# source_eagle.net
KiCad netlist of a schematic drawn in EAGLE
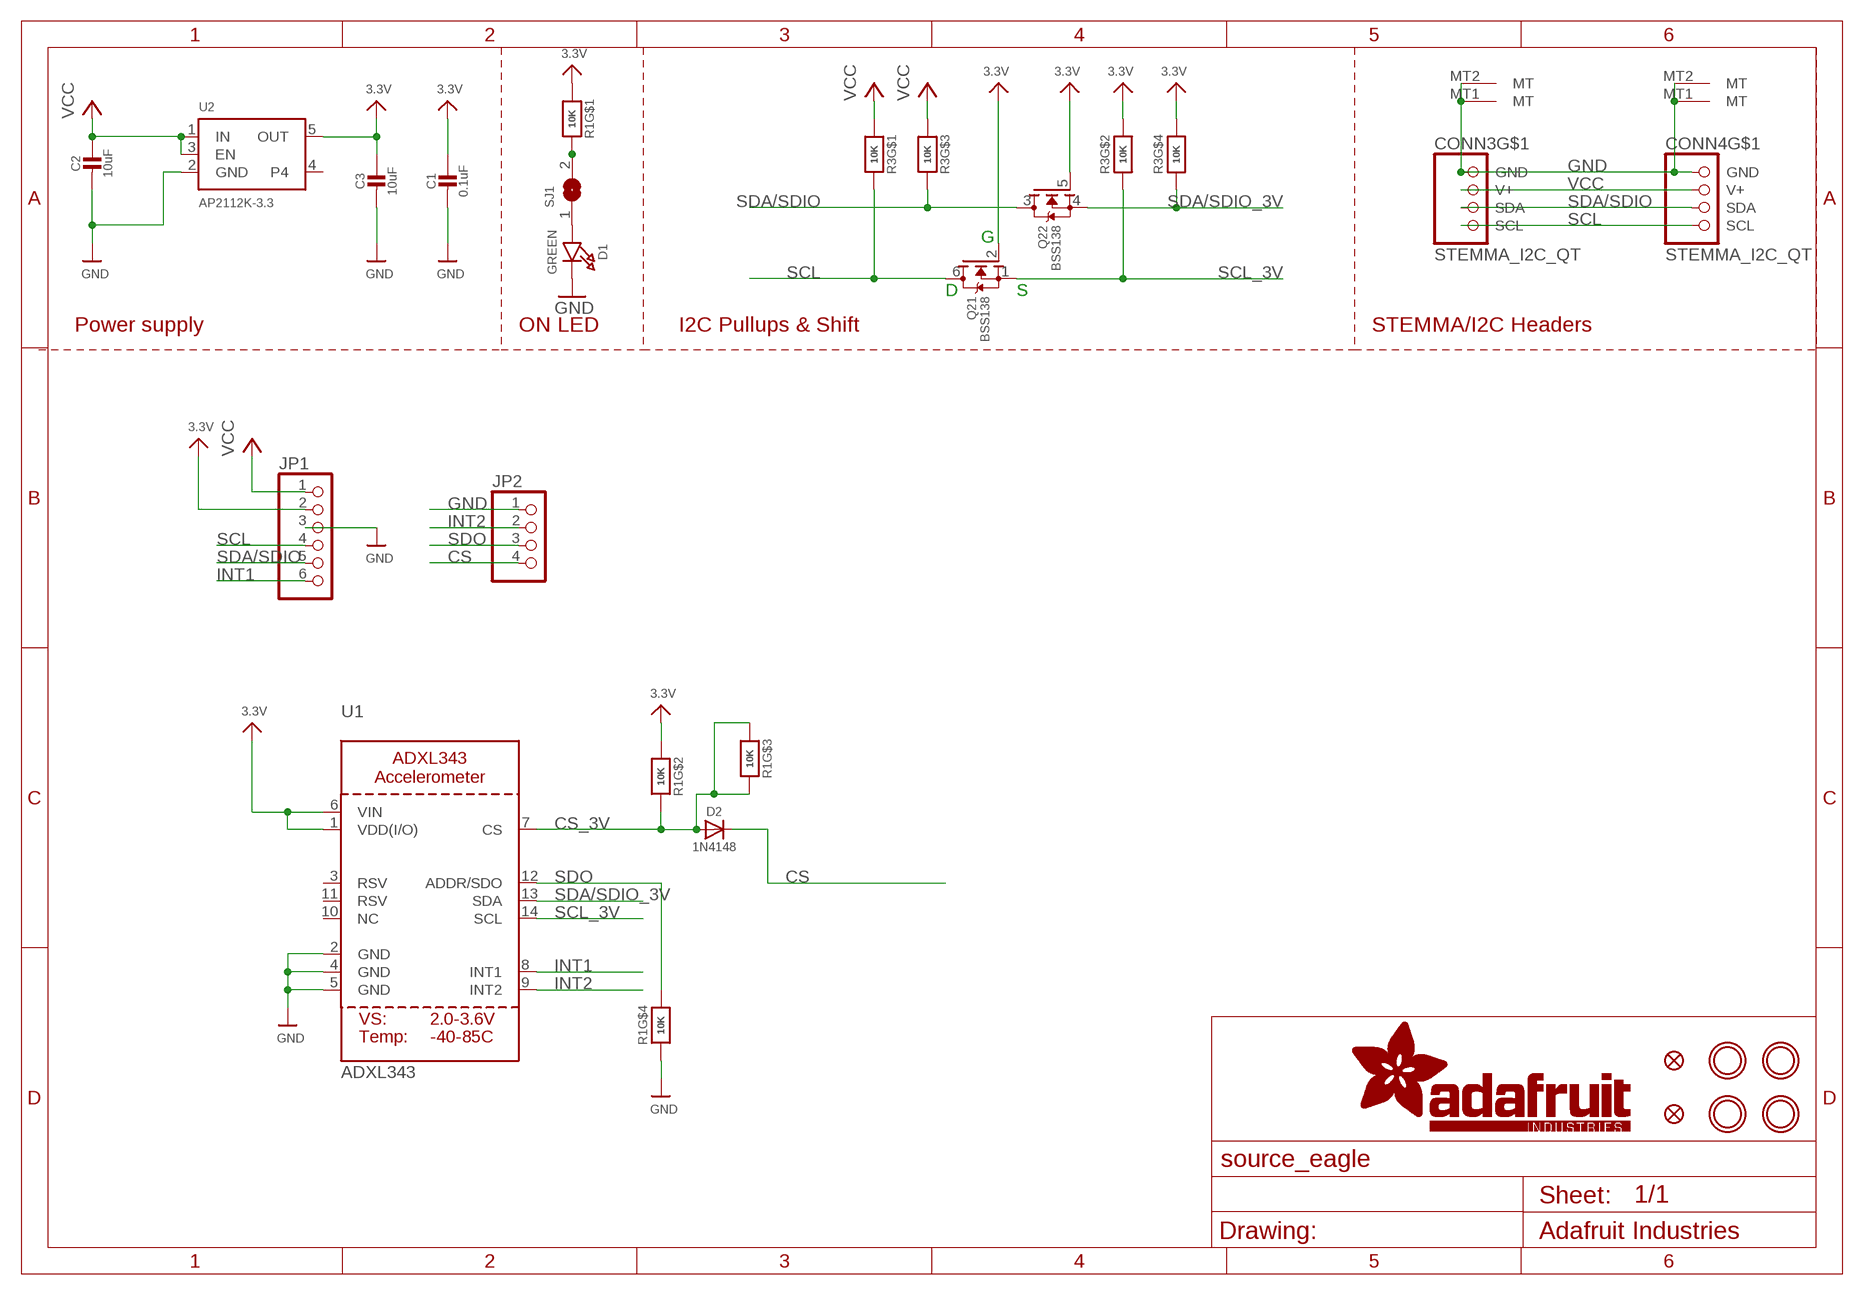
[diagram p0: schematic, sheet 1]

(export (version "E")
  (design (tool "Eeschema 10.0.6"))
  (components
    (comp (ref "C1")
      (value "0.1uF")
      (footprint "eagle-import:0603-NO")
      (libsource (lib "eagle-import") (part "CAP_CERAMIC0603_NO"))
    )
    (comp (ref "C2")
      (value "10uF")
      (footprint "eagle-import:_0805MP")
      (libsource (lib "eagle-import") (part "CAP_CERAMIC_0805MP"))
    )
    (comp (ref "C3")
      (value "10uF")
      (footprint "eagle-import:0805-NO")
      (libsource (lib "eagle-import") (part "CAP_CERAMIC0805-NOOUTLINE"))
    )
    (comp (ref "CONN3")
      (value "STEMMA_I2C_QT")
      (footprint "eagle-import:JST_SH4")
      (libsource (lib "eagle-import") (part "STEMMA_I2C_QT"))
    )
    (comp (ref "CONN4")
      (value "STEMMA_I2C_QT")
      (footprint "eagle-import:JST_SH4")
      (libsource (lib "eagle-import") (part "STEMMA_I2C_QT"))
    )
    (comp (ref "D1")
      (value "GREEN")
      (footprint "eagle-import:CHIPLED_0603_NOOUTLINE")
      (libsource (lib "eagle-import") (part "LED0603_NOOUTLINE"))
    )
    (comp (ref "D2")
      (value "1N4148")
      (footprint "eagle-import:SOD-323")
      (libsource (lib "eagle-import") (part "DIODESOD-323"))
    )
    (comp (ref "FID3")
      (value "FIDUCIAL_1MM")
      (footprint "eagle-import:FIDUCIAL_1MM")
      (libsource (lib "eagle-import") (part "FIDUCIAL_1MM"))
    )
    (comp (ref "FID4")
      (value "FIDUCIAL_1MM")
      (footprint "eagle-import:FIDUCIAL_1MM")
      (libsource (lib "eagle-import") (part "FIDUCIAL_1MM"))
    )
    (comp (ref "JP1")
      (value "HEADER-1X670MIL")
      (footprint "eagle-import:1X06_ROUND_70")
      (libsource (lib "eagle-import") (part "HEADER-1X670MIL"))
    )
    (comp (ref "JP2")
      (value "HEADER-1X4ROUND")
      (footprint "eagle-import:1X04_ROUND")
      (libsource (lib "eagle-import") (part "HEADER-1X4ROUND"))
    )
    (comp (ref "Q2")
      (value "BSS138")
      (footprint "eagle-import:SOT363")
      (libsource (lib "eagle-import") (part "MOSFET-N_DUAL"))
    )
    (comp (ref "R1")
      (value "10K")
      (footprint "eagle-import:RESPACK_4X0603")
      (libsource (lib "eagle-import") (part "RESISTOR_4PACK"))
    )
    (comp (ref "R3")
      (value "10K")
      (footprint "eagle-import:RESPACK_4X0603")
      (libsource (lib "eagle-import") (part "RESISTOR_4PACK"))
    )
    (comp (ref "SJ1")
      (value "SOLDERJUMPERCLOSED")
      (footprint "eagle-import:SOLDERJUMPER_CLOSEDWIRE")
      (libsource (lib "eagle-import") (part "SOLDERJUMPERCLOSED"))
    )
    (comp (ref "U$1")
      (value "MOUNTINGHOLE2.5")
      (footprint "eagle-import:MOUNTINGHOLE_2.5_PLATED")
      (libsource (lib "eagle-import") (part "MOUNTINGHOLE2.5"))
    )
    (comp (ref "U$17")
      (value "MOUNTINGHOLE2.5")
      (footprint "eagle-import:MOUNTINGHOLE_2.5_PLATED")
      (libsource (lib "eagle-import") (part "MOUNTINGHOLE2.5"))
    )
    (comp (ref "U$19")
      (value "MOUNTINGHOLE2.5")
      (footprint "eagle-import:MOUNTINGHOLE_2.5_PLATED")
      (libsource (lib "eagle-import") (part "MOUNTINGHOLE2.5"))
    )
    (comp (ref "U$21")
      (value "MOUNTINGHOLE2.5")
      (footprint "eagle-import:MOUNTINGHOLE_2.5_PLATED")
      (libsource (lib "eagle-import") (part "MOUNTINGHOLE2.5"))
    )
    (comp (ref "U1")
      (value "ADXL343")
      (footprint "eagle-import:LGA14")
      (libsource (lib "eagle-import") (part "ACCEL_ADXL343"))
    )
    (comp (ref "U2")
      (value "AP2112K-3.3")
      (footprint "eagle-import:SOT23-5")
      (libsource (lib "eagle-import") (part "VREG_SOT23-5"))
    )
  )
  (nets
    (net (code "1") (name "/CS") (class "Default")
      (node (ref "D2") (pin "C") (pinfunction "C_C") (pintype "passive"))
      (node (ref "JP2") (pin "4") (pinfunction "4_4") (pintype "passive"))
    )
    (net (code "2") (name "/CS_3V") (class "Default")
      (node (ref "D2") (pin "A") (pinfunction "A_A") (pintype "passive"))
      (node (ref "R1") (pin "3") (pinfunction "1_3") (pintype "passive"))
      (node (ref "R1") (pin "6") (pinfunction "2_6") (pintype "passive"))
      (node (ref "R1") (pin "7") (pinfunction "2_7") (pintype "passive"))
      (node (ref "U1") (pin "7") (pinfunction "CS_7") (pintype "bidirectional"))
    )
    (net (code "3") (name "/INT1") (class "Default")
      (node (ref "JP1") (pin "6") (pinfunction "6_6") (pintype "passive"))
      (node (ref "U1") (pin "8") (pinfunction "INT1_8") (pintype "bidirectional"))
    )
    (net (code "4") (name "/INT2") (class "Default")
      (node (ref "JP2") (pin "2") (pinfunction "2_2") (pintype "passive"))
      (node (ref "U1") (pin "9") (pinfunction "INT2_9") (pintype "bidirectional"))
    )
    (net (code "5") (name "/SCL") (class "Default")
      (node (ref "CONN3") (pin "4") (pinfunction "SCL_4") (pintype "passive"))
      (node (ref "CONN4") (pin "4") (pinfunction "SCL_4") (pintype "passive"))
      (node (ref "JP1") (pin "4") (pinfunction "4_4") (pintype "passive"))
      (node (ref "Q2") (pin "6") (pinfunction "D_6") (pintype "bidirectional"))
      (node (ref "R3") (pin "8") (pinfunction "2_8") (pintype "passive"))
    )
    (net (code "6") (name "/SCL_3V") (class "Default")
      (node (ref "Q2") (pin "1") (pinfunction "S_1") (pintype "bidirectional"))
      (node (ref "R3") (pin "7") (pinfunction "2_7") (pintype "passive"))
      (node (ref "U1") (pin "14") (pinfunction "SCL_14") (pintype "bidirectional"))
    )
    (net (code "7") (name "/SDA{slash}SDIO") (class "Default")
      (node (ref "CONN3") (pin "3") (pinfunction "SDA_3") (pintype "passive"))
      (node (ref "CONN4") (pin "3") (pinfunction "SDA_3") (pintype "passive"))
      (node (ref "JP1") (pin "5") (pinfunction "5_5") (pintype "passive"))
      (node (ref "Q2") (pin "3") (pinfunction "D_3") (pintype "bidirectional"))
      (node (ref "R3") (pin "6") (pinfunction "2_6") (pintype "passive"))
    )
    (net (code "8") (name "/SDA{slash}SDIO_3V") (class "Default")
      (node (ref "Q2") (pin "4") (pinfunction "S_4") (pintype "bidirectional"))
      (node (ref "R3") (pin "5") (pinfunction "2_5") (pintype "passive"))
      (node (ref "U1") (pin "13") (pinfunction "SDA_13") (pintype "bidirectional"))
    )
    (net (code "9") (name "/SDO") (class "Default")
      (node (ref "JP2") (pin "3") (pinfunction "3_3") (pintype "passive"))
      (node (ref "R1") (pin "5") (pinfunction "2_5") (pintype "passive"))
      (node (ref "U1") (pin "12") (pinfunction "ADDR/SDO_12") (pintype "bidirectional"))
    )
    (net (code "10") (name "3.3V") (class "Default")
      (node (ref "C1") (pin "1") (pinfunction "1_1") (pintype "passive"))
      (node (ref "C3") (pin "1") (pinfunction "1_1") (pintype "passive"))
      (node (ref "JP1") (pin "2") (pinfunction "2_2") (pintype "passive"))
      (node (ref "Q2") (pin "2") (pinfunction "G_2") (pintype "bidirectional"))
      (node (ref "Q2") (pin "5") (pinfunction "G_5") (pintype "bidirectional"))
      (node (ref "R1") (pin "1") (pinfunction "1_1") (pintype "passive"))
      (node (ref "R1") (pin "2") (pinfunction "1_2") (pintype "passive"))
      (node (ref "R3") (pin "2") (pinfunction "1_2") (pintype "passive"))
      (node (ref "R3") (pin "4") (pinfunction "1_4") (pintype "passive"))
      (node (ref "U1") (pin "1") (pinfunction "VDD(I/O)_1") (pintype "bidirectional"))
      (node (ref "U1") (pin "6") (pinfunction "VIN_6") (pintype "bidirectional"))
      (node (ref "U2") (pin "5") (pinfunction "OUT_5") (pintype "power_in"))
    )
    (net (code "11") (name "GND") (class "Default")
      (node (ref "C1") (pin "2") (pinfunction "2_2") (pintype "passive"))
      (node (ref "C2") (pin "2") (pinfunction "2_2") (pintype "passive"))
      (node (ref "C3") (pin "2") (pinfunction "2_2") (pintype "passive"))
      (node (ref "CONN3") (pin "1") (pinfunction "GND_1") (pintype "passive"))
      (node (ref "CONN3") (pin "MT1") (pinfunction "MT_MT1") (pintype "bidirectional"))
      (node (ref "CONN3") (pin "MT2") (pinfunction "MT_MT2") (pintype "bidirectional"))
      (node (ref "CONN4") (pin "1") (pinfunction "GND_1") (pintype "passive"))
      (node (ref "CONN4") (pin "MT1") (pinfunction "MT_MT1") (pintype "bidirectional"))
      (node (ref "CONN4") (pin "MT2") (pinfunction "MT_MT2") (pintype "bidirectional"))
      (node (ref "D1") (pin "C") (pinfunction "C_C") (pintype "passive"))
      (node (ref "JP1") (pin "3") (pinfunction "3_3") (pintype "passive"))
      (node (ref "JP2") (pin "1") (pinfunction "1_1") (pintype "passive"))
      (node (ref "R1") (pin "4") (pinfunction "1_4") (pintype "passive"))
      (node (ref "U1") (pin "2") (pinfunction "GND_2") (pintype "bidirectional"))
      (node (ref "U1") (pin "4") (pinfunction "GND_4") (pintype "bidirectional"))
      (node (ref "U1") (pin "5") (pinfunction "GND_5") (pintype "bidirectional"))
      (node (ref "U2") (pin "2") (pinfunction "GND_2") (pintype "power_in"))
    )
    (net (code "12") (name "Net-(D1-PadA)") (class "Default")
      (node (ref "D1") (pin "A") (pinfunction "A_A") (pintype "passive"))
      (node (ref "SJ1") (pin "1") (pinfunction "1_1") (pintype "passive"))
    )
    (net (code "13") (name "Net-(R1A-2)") (class "Default")
      (node (ref "R1") (pin "8") (pinfunction "2_8") (pintype "passive"))
      (node (ref "SJ1") (pin "2") (pinfunction "2_2") (pintype "passive"))
    )
    (net (code "14") (name "VCC") (class "Default")
      (node (ref "C2") (pin "1") (pinfunction "1_1") (pintype "passive"))
      (node (ref "CONN3") (pin "2") (pinfunction "V+_2") (pintype "passive"))
      (node (ref "CONN4") (pin "2") (pinfunction "V+_2") (pintype "passive"))
      (node (ref "JP1") (pin "1") (pinfunction "1_1") (pintype "passive"))
      (node (ref "R3") (pin "1") (pinfunction "1_1") (pintype "passive"))
      (node (ref "R3") (pin "3") (pinfunction "1_3") (pintype "passive"))
      (node (ref "U2") (pin "1") (pinfunction "IN_1") (pintype "power_in"))
      (node (ref "U2") (pin "3") (pinfunction "EN_3") (pintype "input"))
    )
    (net (code "15") (name "unconnected-(U1-NC-Pad10)") (class "Default")
      (node (ref "U1") (pin "10") (pinfunction "NC_10") (pintype "bidirectional"))
    )
    (net (code "16") (name "unconnected-(U1-RSV-Pad3)") (class "Default")
      (node (ref "U1") (pin "3") (pinfunction "RSV_3") (pintype "bidirectional"))
    )
    (net (code "17") (name "unconnected-(U1-RSV-Pad11)") (class "Default")
      (node (ref "U1") (pin "11") (pinfunction "RSV_11") (pintype "bidirectional"))
    )
    (net (code "18") (name "unconnected-(U2-P4-Pad4)") (class "Default")
      (node (ref "U2") (pin "4") (pinfunction "P4_4") (pintype "bidirectional"))
    )
  )
)
